# Circuit_Diagram.net
KiCad netlist of a schematic drawn in EAGLE
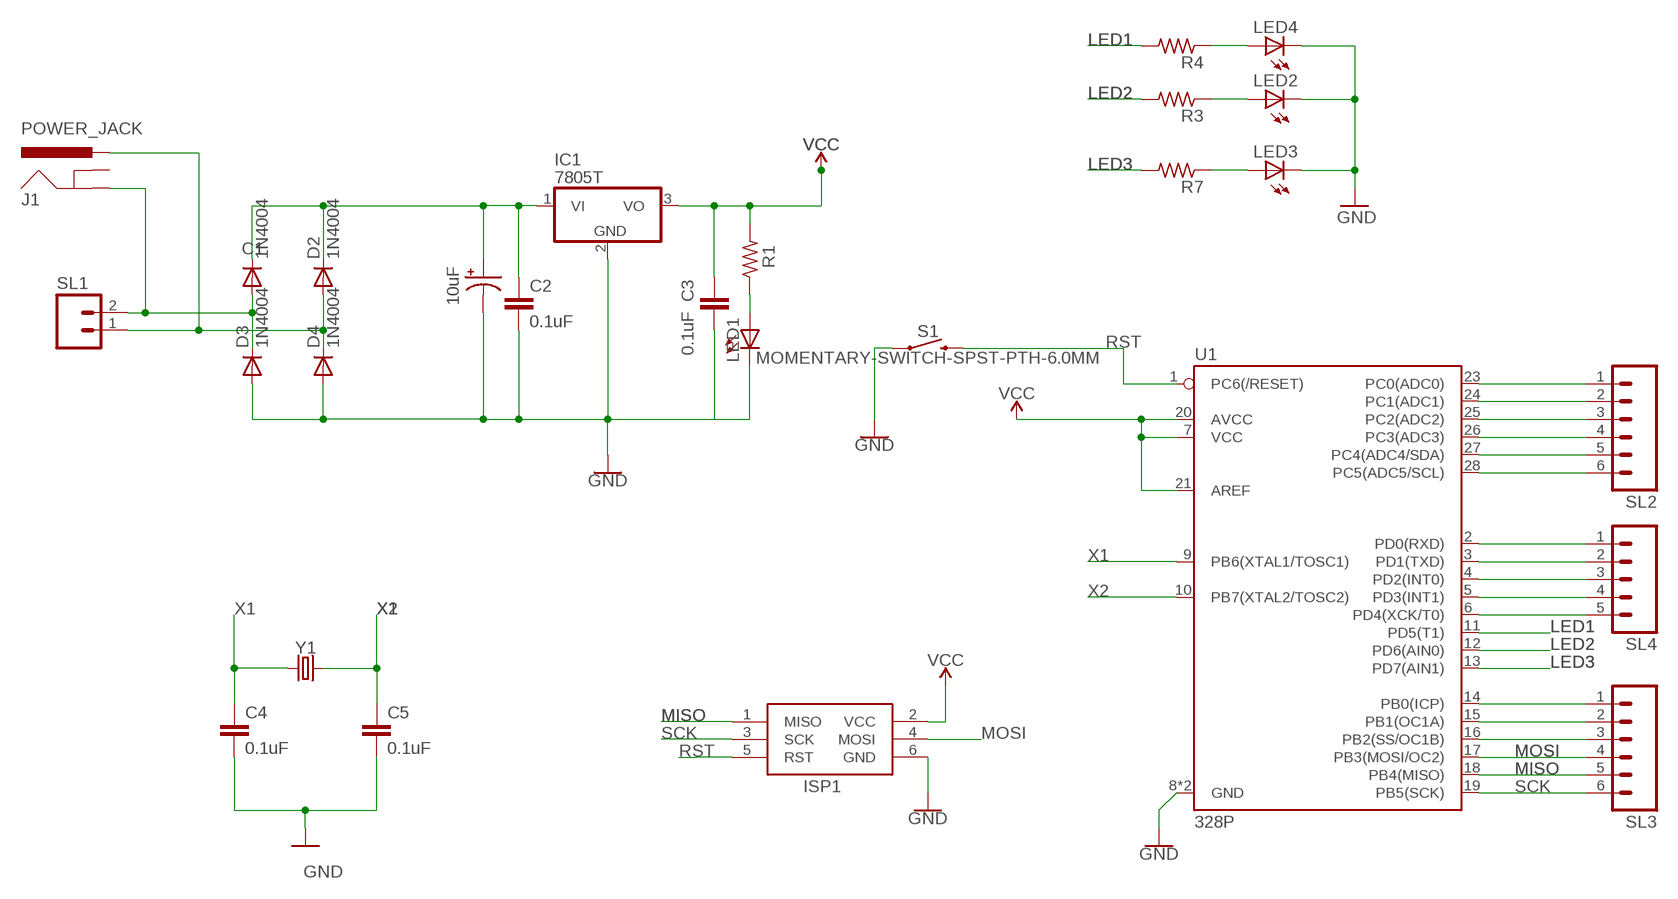
[diagram p0: schematic, sheet 1]

(export (version "E")
  (design (tool "Eeschema 10.0.6"))
  (components
    (comp (ref "C1")
      (value "10uF")
      (footprint "eagle-import:CPOL-RADIAL-2.5MM-5MM")
      (libsource (lib "eagle-import") (part "10UF-POLAR-RADIAL-2.5MM-25V-20%"))
    )
    (comp (ref "C2")
      (value "0.1uF")
      (footprint "eagle-import:CAP-PTH-SMALL-KIT")
      (libsource (lib "eagle-import") (part "0.1UF-KIT-EZ-50V-20%"))
    )
    (comp (ref "C3")
      (value "0.1uF")
      (footprint "eagle-import:CAP-PTH-SMALL-KIT")
      (libsource (lib "eagle-import") (part "0.1UF-KIT-EZ-50V-20%"))
    )
    (comp (ref "C4")
      (value "0.1uF")
      (footprint "eagle-import:CAP-PTH-SMALL-KIT")
      (libsource (lib "eagle-import") (part "0.1UF-KIT-EZ-50V-20%"))
    )
    (comp (ref "C5")
      (value "0.1uF")
      (footprint "eagle-import:CAP-PTH-SMALL-KIT")
      (libsource (lib "eagle-import") (part "0.1UF-KIT-EZ-50V-20%"))
    )
    (comp (ref "D1")
      (value "1N4004")
      (footprint "eagle-import:DO41-10")
      (libsource (lib "eagle-import") (part "1N4004"))
    )
    (comp (ref "D2")
      (value "1N4004")
      (footprint "eagle-import:DO41-10")
      (libsource (lib "eagle-import") (part "1N4004"))
    )
    (comp (ref "D3")
      (value "1N4004")
      (footprint "eagle-import:DO41-10")
      (libsource (lib "eagle-import") (part "1N4004"))
    )
    (comp (ref "D4")
      (value "1N4004")
      (footprint "eagle-import:DO41-10")
      (libsource (lib "eagle-import") (part "1N4004"))
    )
    (comp (ref "IC1")
      (value "7805T")
      (footprint "eagle-import:TO220H")
      (libsource (lib "eagle-import") (part "78T05"))
    )
    (comp (ref "ISP1")
      (value "AVRISP-6")
      (footprint "eagle-import:AVRISP")
      (libsource (lib "eagle-import") (part "AVRISP-6"))
    )
    (comp (ref "J1")
      (value "POWER_JACK")
      (footprint "eagle-import:POWER_JACK_PTH")
      (libsource (lib "eagle-import") (part "POWER_JACK"))
    )
    (comp (ref "LED1")
      (value "LED3MM")
      (footprint "eagle-import:LED3MM")
      (libsource (lib "eagle-import") (part "LED3MM"))
    )
    (comp (ref "LED2")
      (value "LED3MM")
      (footprint "eagle-import:LED3MM")
      (libsource (lib "eagle-import") (part "LED3MM"))
    )
    (comp (ref "LED3")
      (value "LED3MM")
      (footprint "eagle-import:LED3MM")
      (libsource (lib "eagle-import") (part "LED3MM"))
    )
    (comp (ref "LED4")
      (value "LED3MM")
      (footprint "eagle-import:LED3MM")
      (libsource (lib "eagle-import") (part "LED3MM"))
    )
    (comp (ref "R1")
      (value "R-US_0207/9")
      (footprint "eagle-import:0207_9")
      (libsource (lib "eagle-import") (part "R-US_0207/9"))
    )
    (comp (ref "R3")
      (value "R-US_0207/9")
      (footprint "eagle-import:0207_9")
      (libsource (lib "eagle-import") (part "R-US_0207/9"))
    )
    (comp (ref "R4")
      (value "R-US_0207/9")
      (footprint "eagle-import:0207_9")
      (libsource (lib "eagle-import") (part "R-US_0207/9"))
    )
    (comp (ref "R7")
      (value "R-US_0207/9")
      (footprint "eagle-import:0207_9")
      (libsource (lib "eagle-import") (part "R-US_0207/9"))
    )
    (comp (ref "S1")
      (value "MOMENTARY-SWITCH-SPST-PTH-6.0MM")
      (footprint "eagle-import:TACTILE_SWITCH_PTH_6.0MM")
      (libsource (lib "eagle-import") (part "MOMENTARY-SWITCH-SPST-PTH-6.0MM"))
    )
    (comp (ref "SL1")
      (value "M02")
      (footprint "eagle-import:02P")
      (libsource (lib "eagle-import") (part "M02"))
    )
    (comp (ref "SL2")
      (value "M06")
      (footprint "eagle-import:06P")
      (libsource (lib "eagle-import") (part "M06"))
    )
    (comp (ref "SL3")
      (value "M06")
      (footprint "eagle-import:06P")
      (libsource (lib "eagle-import") (part "M06"))
    )
    (comp (ref "SL4")
      (value "M05")
      (footprint "eagle-import:05P")
      (libsource (lib "eagle-import") (part "M05"))
    )
    (comp (ref "U1")
      (value "328P")
      (footprint "eagle-import:DIP28")
      (libsource (lib "eagle-import") (part "ATMEGA328P_PDIP"))
    )
    (comp (ref "Y1")
      (value "CRYSTALPTH-HC49US")
      (footprint "eagle-import:HC49US")
      (libsource (lib "eagle-import") (part "CRYSTALPTH-HC49US"))
    )
  )
  (nets
    (net (code "1") (name "/LED1") (class "Default")
      (node (ref "R4") (pin "2") (pinfunction "2_2") (pintype "passive"))
      (node (ref "U1") (pin "11") (pinfunction "PD5(T1)_11") (pintype "bidirectional"))
    )
    (net (code "2") (name "/LED2") (class "Default")
      (node (ref "R3") (pin "2") (pinfunction "2_2") (pintype "passive"))
      (node (ref "U1") (pin "12") (pinfunction "PD6(AIN0)_12") (pintype "bidirectional"))
    )
    (net (code "3") (name "/LED3") (class "Default")
      (node (ref "R7") (pin "2") (pinfunction "2_2") (pintype "passive"))
      (node (ref "U1") (pin "13") (pinfunction "PD7(AIN1)_13") (pintype "bidirectional"))
    )
    (net (code "4") (name "/MISO") (class "Default")
      (node (ref "ISP1") (pin "1") (pinfunction "MISO_1") (pintype "input"))
      (node (ref "SL3") (pin "5") (pinfunction "5_5") (pintype "passive"))
      (node (ref "U1") (pin "18") (pinfunction "PB4(MISO)_18") (pintype "bidirectional"))
    )
    (net (code "5") (name "/MOSI") (class "Default")
      (node (ref "ISP1") (pin "4") (pinfunction "MOSI_4") (pintype "output"))
      (node (ref "SL3") (pin "4") (pinfunction "4_4") (pintype "passive"))
      (node (ref "U1") (pin "17") (pinfunction "PB3(MOSI/OC2)_17") (pintype "bidirectional"))
    )
    (net (code "6") (name "/RST") (class "Default")
      (node (ref "ISP1") (pin "5") (pinfunction "RST_5") (pintype "output"))
      (node (ref "S1") (pin "3") (pinfunction "2_3") (pintype "passive"))
      (node (ref "U1") (pin "1") (pinfunction "PC6(/RESET)_1") (pintype "bidirectional"))
    )
    (net (code "7") (name "/SCK") (class "Default")
      (node (ref "ISP1") (pin "3") (pinfunction "SCK_3") (pintype "output"))
      (node (ref "SL3") (pin "6") (pinfunction "6_6") (pintype "passive"))
      (node (ref "U1") (pin "19") (pinfunction "PB5(SCK)_19") (pintype "bidirectional"))
    )
    (net (code "8") (name "/X1") (class "Default")
      (node (ref "C4") (pin "1") (pinfunction "1_1") (pintype "passive"))
      (node (ref "U1") (pin "9") (pinfunction "PB6(XTAL1/TOSC1)_9") (pintype "bidirectional"))
      (node (ref "Y1") (pin "1") (pinfunction "1_1") (pintype "passive"))
    )
    (net (code "9") (name "/X2") (class "Default")
      (node (ref "C5") (pin "1") (pinfunction "1_1") (pintype "passive"))
      (node (ref "U1") (pin "10") (pinfunction "PB7(XTAL2/TOSC2)_10") (pintype "bidirectional"))
      (node (ref "Y1") (pin "2") (pinfunction "2_2") (pintype "passive"))
    )
    (net (code "10") (name "GND") (class "Default")
      (node (ref "C1") (pin "2") (pinfunction "-_2") (pintype "passive"))
      (node (ref "C2") (pin "2") (pinfunction "2_2") (pintype "passive"))
      (node (ref "C3") (pin "2") (pinfunction "2_2") (pintype "passive"))
      (node (ref "C4") (pin "2") (pinfunction "2_2") (pintype "passive"))
      (node (ref "C5") (pin "2") (pinfunction "2_2") (pintype "passive"))
      (node (ref "D3") (pin "A") (pinfunction "A_A") (pintype "passive"))
      (node (ref "D4") (pin "A") (pinfunction "A_A") (pintype "passive"))
      (node (ref "IC1") (pin "2") (pinfunction "GND_2") (pintype "passive"))
      (node (ref "ISP1") (pin "6") (pinfunction "GND_6") (pintype "power_in"))
      (node (ref "LED1") (pin "K") (pinfunction "C_K") (pintype "passive"))
      (node (ref "LED2") (pin "K") (pinfunction "C_K") (pintype "passive"))
      (node (ref "LED3") (pin "K") (pinfunction "C_K") (pintype "passive"))
      (node (ref "LED4") (pin "K") (pinfunction "C_K") (pintype "passive"))
      (node (ref "S1") (pin "1") (pinfunction "1_1") (pintype "passive"))
      (node (ref "U1") (pin "22") (pinfunction "GND_22") (pintype "bidirectional"))
      (node (ref "U1") (pin "8") (pinfunction "GND_8") (pintype "bidirectional"))
    )
    (net (code "11") (name "Net-(C1-+)") (class "Default")
      (node (ref "C1") (pin "1") (pinfunction "+_1") (pintype "passive"))
      (node (ref "C2") (pin "1") (pinfunction "1_1") (pintype "passive"))
      (node (ref "D1") (pin "C") (pinfunction "C_C") (pintype "passive"))
      (node (ref "D2") (pin "C") (pinfunction "C_C") (pintype "passive"))
      (node (ref "IC1") (pin "1") (pinfunction "VI_1") (pintype "input"))
    )
    (net (code "12") (name "Net-(D1-PadA)") (class "Default")
      (node (ref "D1") (pin "A") (pinfunction "A_A") (pintype "passive"))
      (node (ref "D3") (pin "C") (pinfunction "C_C") (pintype "passive"))
      (node (ref "J1") (pin "GND") (pinfunction "GND_GND") (pintype "bidirectional"))
      (node (ref "SL1") (pin "2") (pinfunction "2_2") (pintype "passive"))
    )
    (net (code "13") (name "Net-(D2-PadA)") (class "Default")
      (node (ref "D2") (pin "A") (pinfunction "A_A") (pintype "passive"))
      (node (ref "D4") (pin "C") (pinfunction "C_C") (pintype "passive"))
      (node (ref "J1") (pin "PWR") (pinfunction "PWR_PWR") (pintype "bidirectional"))
      (node (ref "SL1") (pin "1") (pinfunction "1_1") (pintype "passive"))
    )
    (net (code "14") (name "Net-(LED1-PadA)") (class "Default")
      (node (ref "LED1") (pin "A") (pinfunction "A_A") (pintype "passive"))
      (node (ref "R1") (pin "1") (pinfunction "1_1") (pintype "passive"))
    )
    (net (code "15") (name "Net-(LED2-PadA)") (class "Default")
      (node (ref "LED2") (pin "A") (pinfunction "A_A") (pintype "passive"))
      (node (ref "R3") (pin "1") (pinfunction "1_1") (pintype "passive"))
    )
    (net (code "16") (name "Net-(LED3-PadA)") (class "Default")
      (node (ref "LED3") (pin "A") (pinfunction "A_A") (pintype "passive"))
      (node (ref "R7") (pin "1") (pinfunction "1_1") (pintype "passive"))
    )
    (net (code "17") (name "Net-(LED4-PadA)") (class "Default")
      (node (ref "LED4") (pin "A") (pinfunction "A_A") (pintype "passive"))
      (node (ref "R4") (pin "1") (pinfunction "1_1") (pintype "passive"))
    )
    (net (code "18") (name "Net-(U1-PB0(ICP))") (class "Default")
      (node (ref "SL3") (pin "1") (pinfunction "1_1") (pintype "passive"))
      (node (ref "U1") (pin "14") (pinfunction "PB0(ICP)_14") (pintype "bidirectional"))
    )
    (net (code "19") (name "Net-(U1-PB1(OC1A))") (class "Default")
      (node (ref "SL3") (pin "2") (pinfunction "2_2") (pintype "passive"))
      (node (ref "U1") (pin "15") (pinfunction "PB1(OC1A)_15") (pintype "bidirectional"))
    )
    (net (code "20") (name "Net-(U1-PB2(SS{slash}OC1B))") (class "Default")
      (node (ref "SL3") (pin "3") (pinfunction "3_3") (pintype "passive"))
      (node (ref "U1") (pin "16") (pinfunction "PB2(SS/OC1B)_16") (pintype "bidirectional"))
    )
    (net (code "21") (name "Net-(U1-PC0(ADC0))") (class "Default")
      (node (ref "SL2") (pin "1") (pinfunction "1_1") (pintype "passive"))
      (node (ref "U1") (pin "23") (pinfunction "PC0(ADC0)_23") (pintype "bidirectional"))
    )
    (net (code "22") (name "Net-(U1-PC1(ADC1))") (class "Default")
      (node (ref "SL2") (pin "2") (pinfunction "2_2") (pintype "passive"))
      (node (ref "U1") (pin "24") (pinfunction "PC1(ADC1)_24") (pintype "bidirectional"))
    )
    (net (code "23") (name "Net-(U1-PC2(ADC2))") (class "Default")
      (node (ref "SL2") (pin "3") (pinfunction "3_3") (pintype "passive"))
      (node (ref "U1") (pin "25") (pinfunction "PC2(ADC2)_25") (pintype "bidirectional"))
    )
    (net (code "24") (name "Net-(U1-PC3(ADC3))") (class "Default")
      (node (ref "SL2") (pin "4") (pinfunction "4_4") (pintype "passive"))
      (node (ref "U1") (pin "26") (pinfunction "PC3(ADC3)_26") (pintype "bidirectional"))
    )
    (net (code "25") (name "Net-(U1-PC4(ADC4{slash}SDA))") (class "Default")
      (node (ref "SL2") (pin "5") (pinfunction "5_5") (pintype "passive"))
      (node (ref "U1") (pin "27") (pinfunction "PC4(ADC4/SDA)_27") (pintype "bidirectional"))
    )
    (net (code "26") (name "Net-(U1-PC5(ADC5{slash}SCL))") (class "Default")
      (node (ref "SL2") (pin "6") (pinfunction "6_6") (pintype "passive"))
      (node (ref "U1") (pin "28") (pinfunction "PC5(ADC5/SCL)_28") (pintype "bidirectional"))
    )
    (net (code "27") (name "Net-(U1-PD0(RXD))") (class "Default")
      (node (ref "SL4") (pin "1") (pinfunction "1_1") (pintype "passive"))
      (node (ref "U1") (pin "2") (pinfunction "PD0(RXD)_2") (pintype "bidirectional"))
    )
    (net (code "28") (name "Net-(U1-PD1(TXD))") (class "Default")
      (node (ref "SL4") (pin "2") (pinfunction "2_2") (pintype "passive"))
      (node (ref "U1") (pin "3") (pinfunction "PD1(TXD)_3") (pintype "bidirectional"))
    )
    (net (code "29") (name "Net-(U1-PD2(INT0))") (class "Default")
      (node (ref "SL4") (pin "3") (pinfunction "3_3") (pintype "passive"))
      (node (ref "U1") (pin "4") (pinfunction "PD2(INT0)_4") (pintype "bidirectional"))
    )
    (net (code "30") (name "Net-(U1-PD3(INT1))") (class "Default")
      (node (ref "SL4") (pin "4") (pinfunction "4_4") (pintype "passive"))
      (node (ref "U1") (pin "5") (pinfunction "PD3(INT1)_5") (pintype "bidirectional"))
    )
    (net (code "31") (name "Net-(U1-PD4(XCK{slash}T0))") (class "Default")
      (node (ref "SL4") (pin "5") (pinfunction "5_5") (pintype "passive"))
      (node (ref "U1") (pin "6") (pinfunction "PD4(XCK/T0)_6") (pintype "bidirectional"))
    )
    (net (code "32") (name "VCC") (class "Default")
      (node (ref "C3") (pin "1") (pinfunction "1_1") (pintype "passive"))
      (node (ref "IC1") (pin "3") (pinfunction "VO_3") (pintype "passive"))
      (node (ref "ISP1") (pin "2") (pinfunction "VCC_2") (pintype "power_in"))
      (node (ref "R1") (pin "2") (pinfunction "2_2") (pintype "passive"))
      (node (ref "U1") (pin "20") (pinfunction "AVCC_20") (pintype "bidirectional"))
      (node (ref "U1") (pin "21") (pinfunction "AREF_21") (pintype "bidirectional"))
      (node (ref "U1") (pin "7") (pinfunction "VCC_7") (pintype "bidirectional"))
    )
    (net (code "33") (name "unconnected-(J1-PadGNDBREAK)") (class "Default")
      (node (ref "J1") (pin "GNDBREAK") (pinfunction "GNDBREAK_GNDBREAK") (pintype "bidirectional"))
    )
  )
)
